# Back_Board.net
KiCad netlist of a schematic drawn in Altium Designer
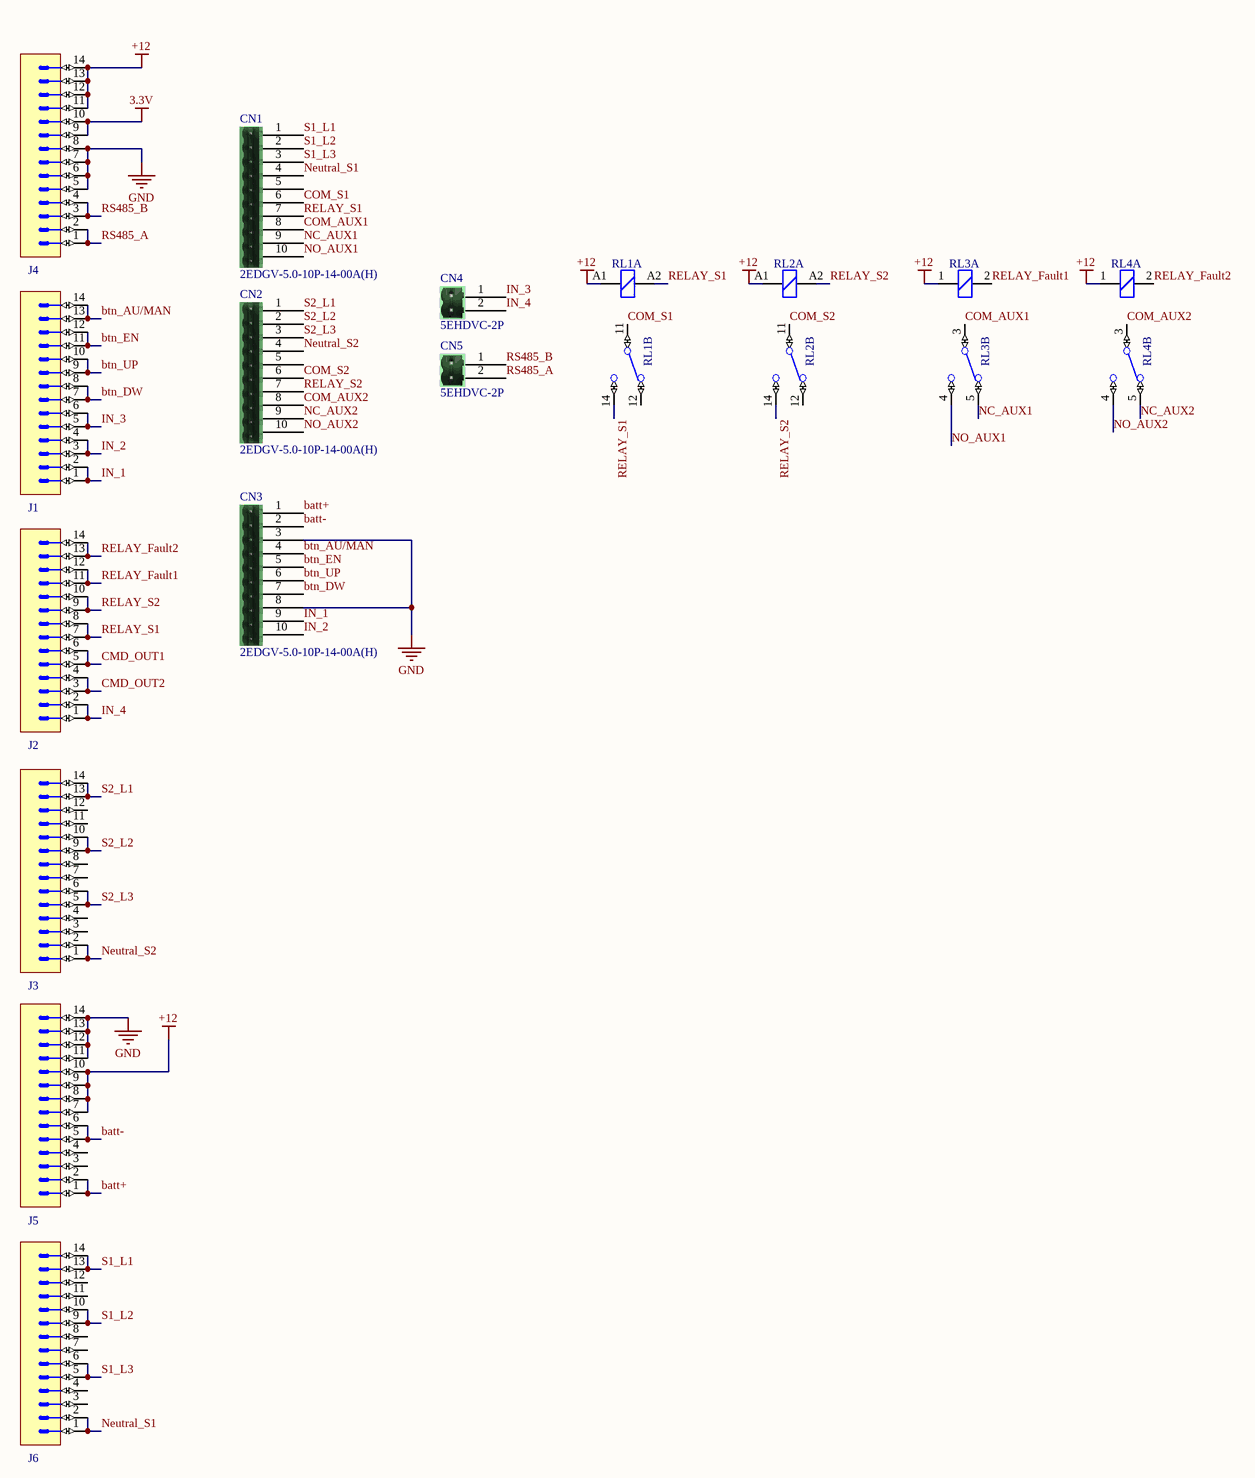
[diagram p0: Back_Board.SchDoc]

(export (version "E")
  (design (tool "Eeschema 10.0.6"))
  (components
    (comp (ref "CN1")
      (value "2EDGV-5.0-10P-14-00A(H)")
      (footprint "0330-0097-8_2EDGV-5.0-10P-14-00A(H)")
      (description "Plug-in Terminal Block 10pins,Male,300V/15A  Pitch 5.0mm")
      (fields (field (name "ES PART NUMBER") "0330-0097-8"))
      (libsource (lib "ES Terminal Blocks") (part "0330-0097-8_2EDGV-5.0-10P-14-00A(H)"))
    )
    (comp (ref "CN2")
      (value "2EDGV-5.0-10P-14-00A(H)")
      (footprint "0330-0097-8_2EDGV-5.0-10P-14-00A(H)")
      (description "Plug-in Terminal Block 10pins,Male,300V/15A  Pitch 5.0mm")
      (fields (field (name "ES PART NUMBER") "0330-0097-8"))
      (libsource (lib "ES Terminal Blocks") (part "0330-0097-8_2EDGV-5.0-10P-14-00A(H)"))
    )
    (comp (ref "CN3")
      (value "2EDGV-5.0-10P-14-00A(H)")
      (footprint "0330-0097-8_2EDGV-5.0-10P-14-00A(H)")
      (description "Plug-in Terminal Block 10pins,Male,300V/15A  Pitch 5.0mm")
      (fields (field (name "ES PART NUMBER") "0330-0097-8"))
      (libsource (lib "ES Terminal Blocks") (part "0330-0097-8_2EDGV-5.0-10P-14-00A(H)"))
    )
    (comp (ref "CN4")
      (value "5EHDVC-2P")
      (footprint "0005-0113-3_5EHDVC-2P")
      (description "Plug-in Terminal Block 2pins,Male,300V/15A  Pitch 5.00mm")
      (fields (field (name "ES PART NUMBER") "0005-0113-3"))
      (libsource (lib "ES Terminal Blocks") (part "0005-0113-3_5EHDVC-2P"))
    )
    (comp (ref "CN5")
      (value "5EHDVC-2P")
      (footprint "0005-0113-3_5EHDVC-2P")
      (description "Plug-in Terminal Block 2pins,Male,300V/15A  Pitch 5.00mm")
      (fields (field (name "ES PART NUMBER") "0005-0113-3"))
      (libsource (lib "ES Terminal Blocks") (part "0005-0113-3_5EHDVC-2P"))
    )
    (comp (ref "J1")
      (value "Header 14")
      (footprint "COMATEL_389.0358.1.14.400")
      (description "Connector 14 Male")
      (fields
        (field (name "PART NUMBER") "COMATEL_389.0358.1.14.400")
        (field (name "MANUFACTURER") "KONTEK COMATEL")
        (field (name "AUTHOR") "CERN DEM JLC")
      )
      (libsource (lib "Connectors") (part "Connector 14 Male"))
    )
    (comp (ref "J2")
      (value "Header 14")
      (footprint "COMATEL_389.0358.1.14.400")
      (description "Connector 14 Male")
      (fields
        (field (name "PART NUMBER") "COMATEL_389.0358.1.14.400")
        (field (name "MANUFACTURER") "KONTEK COMATEL")
        (field (name "AUTHOR") "CERN DEM JLC")
      )
      (libsource (lib "Connectors") (part "Connector 14 Male"))
    )
    (comp (ref "J3")
      (value "Header 14")
      (footprint "COMATEL_389.0358.1.14.400")
      (description "Connector 14 Male")
      (fields
        (field (name "PART NUMBER") "COMATEL_389.0358.1.14.400")
        (field (name "MANUFACTURER") "KONTEK COMATEL")
        (field (name "AUTHOR") "CERN DEM JLC")
      )
      (libsource (lib "Connectors") (part "Connector 14 Male"))
    )
    (comp (ref "J4")
      (value "Header 14")
      (footprint "COMATEL_389.0358.1.14.400")
      (description "Connector 14 Male")
      (fields
        (field (name "PART NUMBER") "COMATEL_389.0358.1.14.400")
        (field (name "MANUFACTURER") "KONTEK COMATEL")
        (field (name "AUTHOR") "CERN DEM JLC")
      )
      (libsource (lib "Connectors") (part "Connector 14 Male"))
    )
    (comp (ref "J5")
      (value "Header 14")
      (footprint "COMATEL_389.0358.1.14.400")
      (description "Connector 14 Male")
      (fields
        (field (name "PART NUMBER") "COMATEL_389.0358.1.14.400")
        (field (name "MANUFACTURER") "KONTEK COMATEL")
        (field (name "AUTHOR") "CERN DEM JLC")
      )
      (libsource (lib "Connectors") (part "Connector 14 Male"))
    )
    (comp (ref "J6")
      (value "Header 14")
      (footprint "COMATEL_389.0358.1.14.400")
      (description "Connector 14 Male")
      (fields
        (field (name "PART NUMBER") "COMATEL_389.0358.1.14.400")
        (field (name "MANUFACTURER") "KONTEK COMATEL")
        (field (name "AUTHOR") "CERN DEM JLC")
      )
      (libsource (lib "Connectors") (part "Connector 14 Male"))
    )
    (comp (ref "RL1")
      (value "12VDC")
      (footprint "REL_TYCO_SCHRACK_RT31XXXX")
      (description "RT PCB Relay Form C (1 CO Contact)")
      (fields
        (field (name "PART NUMBER") "REL_TYCO_SCHRACK_RT314012")
        (field (name "MANUFACTURER") "TYCO SCHRACK")
        (field (name "AUTHOR") "CERN DEM JLC")
      )
      (libsource (lib "Eletro-mechanical") (part "REL_TYCO_SCHRACK_RT31xxxx"))
    )
    (comp (ref "RL2")
      (value "12VDC")
      (footprint "REL_TYCO_SCHRACK_RT31XXXX")
      (description "RT PCB Relay Form C (1 CO Contact)")
      (fields
        (field (name "PART NUMBER") "REL_TYCO_SCHRACK_RT314012")
        (field (name "MANUFACTURER") "TYCO SCHRACK")
        (field (name "AUTHOR") "CERN DEM JLC")
      )
      (libsource (lib "Eletro-mechanical") (part "REL_TYCO_SCHRACK_RT31xxxx"))
    )
    (comp (ref "RL3")
      (value "5VDC")
      (footprint "REL_FINDER_36.11")
      (description "10A SPDT PCB Relay, 36 Serie")
      (fields
        (field (name "PART NUMBER") "REL_FINDER_36.11.9.005.4001")
        (field (name "MANUFACTURER") "FINDER")
        (field (name "AUTHOR") "CERN DEM JLC")
      )
      (libsource (lib "Eletro-mechanical") (part "REL_FINDER_36.11-4001"))
    )
    (comp (ref "RL4")
      (value "5VDC")
      (footprint "REL_FINDER_36.11")
      (description "10A SPDT PCB Relay, 36 Serie")
      (fields
        (field (name "PART NUMBER") "REL_FINDER_36.11.9.005.4001")
        (field (name "MANUFACTURER") "FINDER")
        (field (name "AUTHOR") "CERN DEM JLC")
      )
      (libsource (lib "Eletro-mechanical") (part "REL_FINDER_36.11-4001"))
    )
  )
  (nets
    (net (code "1") (name "+12") (class "Default")
      (node (ref "J4") (pin "11") (pinfunction "11_11") (pintype "bidirectional"))
      (node (ref "J4") (pin "12") (pinfunction "12_12") (pintype "bidirectional"))
      (node (ref "J4") (pin "13") (pinfunction "13_13") (pintype "bidirectional"))
      (node (ref "J4") (pin "14") (pinfunction "14_14") (pintype "bidirectional"))
      (node (ref "J5") (pin "10") (pinfunction "10_10") (pintype "bidirectional"))
      (node (ref "J5") (pin "7") (pinfunction "7_7") (pintype "bidirectional"))
      (node (ref "J5") (pin "8") (pinfunction "8_8") (pintype "bidirectional"))
      (node (ref "J5") (pin "9") (pinfunction "9_9") (pintype "bidirectional"))
      (node (ref "RL1") (pin "A1") (pinfunction "A1_A1") (pintype "passive"))
      (node (ref "RL2") (pin "A1") (pinfunction "A1_A1") (pintype "passive"))
      (node (ref "RL3") (pin "1") (pinfunction "COIL_1") (pintype "passive"))
      (node (ref "RL4") (pin "1") (pinfunction "COIL_1") (pintype "passive"))
    )
    (net (code "2") (name "/CMD_OUT1") (class "Default")
      (node (ref "J2") (pin "5") (pinfunction "5_5") (pintype "bidirectional"))
      (node (ref "J2") (pin "6") (pinfunction "6_6") (pintype "bidirectional"))
    )
    (net (code "3") (name "/CMD_OUT2") (class "Default")
      (node (ref "J2") (pin "3") (pinfunction "3_3") (pintype "bidirectional"))
      (node (ref "J2") (pin "4") (pinfunction "4_4") (pintype "bidirectional"))
    )
    (net (code "4") (name "/COM_AUX1") (class "Default")
      (node (ref "CN1") (pin "8") (pinfunction "8_8") (pintype "passive"))
      (node (ref "RL3") (pin "3") (pinfunction "C_3") (pintype "bidirectional"))
    )
    (net (code "5") (name "/COM_AUX2") (class "Default")
      (node (ref "CN2") (pin "8") (pinfunction "8_8") (pintype "passive"))
      (node (ref "RL4") (pin "3") (pinfunction "C_3") (pintype "bidirectional"))
    )
    (net (code "6") (name "/COM_S1") (class "Default")
      (node (ref "CN1") (pin "6") (pinfunction "6_6") (pintype "passive"))
      (node (ref "RL1") (pin "11") (pinfunction "C_11") (pintype "bidirectional"))
    )
    (net (code "7") (name "/COM_S2") (class "Default")
      (node (ref "CN2") (pin "6") (pinfunction "6_6") (pintype "passive"))
      (node (ref "RL2") (pin "11") (pinfunction "C_11") (pintype "bidirectional"))
    )
    (net (code "8") (name "/IN_1") (class "Default")
      (node (ref "CN3") (pin "9") (pinfunction "9_9") (pintype "passive"))
      (node (ref "J1") (pin "1") (pinfunction "1_1") (pintype "bidirectional"))
      (node (ref "J1") (pin "2") (pinfunction "2_2") (pintype "bidirectional"))
    )
    (net (code "9") (name "/IN_2") (class "Default")
      (node (ref "CN3") (pin "10") (pinfunction "10_10") (pintype "passive"))
      (node (ref "J1") (pin "3") (pinfunction "3_3") (pintype "bidirectional"))
      (node (ref "J1") (pin "4") (pinfunction "4_4") (pintype "bidirectional"))
    )
    (net (code "10") (name "/IN_3") (class "Default")
      (node (ref "CN4") (pin "1") (pinfunction "1_1") (pintype "passive"))
      (node (ref "J1") (pin "5") (pinfunction "5_5") (pintype "bidirectional"))
      (node (ref "J1") (pin "6") (pinfunction "6_6") (pintype "bidirectional"))
    )
    (net (code "11") (name "/IN_4") (class "Default")
      (node (ref "CN4") (pin "2") (pinfunction "2_2") (pintype "passive"))
      (node (ref "J2") (pin "1") (pinfunction "1_1") (pintype "bidirectional"))
      (node (ref "J2") (pin "2") (pinfunction "2_2") (pintype "bidirectional"))
    )
    (net (code "12") (name "/NC_AUX1") (class "Default")
      (node (ref "CN1") (pin "9") (pinfunction "9_9") (pintype "passive"))
      (node (ref "RL3") (pin "5") (pinfunction "NC_5") (pintype "bidirectional"))
    )
    (net (code "13") (name "/NC_AUX2") (class "Default")
      (node (ref "CN2") (pin "9") (pinfunction "9_9") (pintype "passive"))
      (node (ref "RL4") (pin "5") (pinfunction "NC_5") (pintype "bidirectional"))
    )
    (net (code "14") (name "/NO_AUX1") (class "Default")
      (node (ref "CN1") (pin "10") (pinfunction "10_10") (pintype "passive"))
      (node (ref "RL3") (pin "4") (pinfunction "NO_4") (pintype "bidirectional"))
    )
    (net (code "15") (name "/NO_AUX2") (class "Default")
      (node (ref "CN2") (pin "10") (pinfunction "10_10") (pintype "passive"))
      (node (ref "RL4") (pin "4") (pinfunction "NO_4") (pintype "bidirectional"))
    )
    (net (code "16") (name "/Neutral_S1") (class "Default")
      (node (ref "CN1") (pin "4") (pinfunction "4_4") (pintype "passive"))
      (node (ref "J6") (pin "1") (pinfunction "1_1") (pintype "bidirectional"))
      (node (ref "J6") (pin "2") (pinfunction "2_2") (pintype "bidirectional"))
    )
    (net (code "17") (name "/Neutral_S2") (class "Default")
      (node (ref "CN2") (pin "4") (pinfunction "4_4") (pintype "passive"))
      (node (ref "J3") (pin "1") (pinfunction "1_1") (pintype "bidirectional"))
      (node (ref "J3") (pin "2") (pinfunction "2_2") (pintype "bidirectional"))
    )
    (net (code "18") (name "/RELAY_Fault1") (class "Default")
      (node (ref "J2") (pin "11") (pinfunction "11_11") (pintype "bidirectional"))
      (node (ref "J2") (pin "12") (pinfunction "12_12") (pintype "bidirectional"))
      (node (ref "RL3") (pin "2") (pinfunction "COIL_2") (pintype "passive"))
    )
    (net (code "19") (name "/RELAY_Fault2") (class "Default")
      (node (ref "J2") (pin "13") (pinfunction "13_13") (pintype "bidirectional"))
      (node (ref "J2") (pin "14") (pinfunction "14_14") (pintype "bidirectional"))
      (node (ref "RL4") (pin "2") (pinfunction "COIL_2") (pintype "passive"))
    )
    (net (code "20") (name "/RELAY_S1") (class "Default")
      (node (ref "CN1") (pin "7") (pinfunction "7_7") (pintype "passive"))
      (node (ref "J2") (pin "7") (pinfunction "7_7") (pintype "bidirectional"))
      (node (ref "J2") (pin "8") (pinfunction "8_8") (pintype "bidirectional"))
      (node (ref "RL1") (pin "14") (pinfunction "NO_14") (pintype "bidirectional"))
      (node (ref "RL1") (pin "A2") (pinfunction "A2_A2") (pintype "passive"))
    )
    (net (code "21") (name "/RELAY_S2") (class "Default")
      (node (ref "CN2") (pin "7") (pinfunction "7_7") (pintype "passive"))
      (node (ref "J2") (pin "10") (pinfunction "10_10") (pintype "bidirectional"))
      (node (ref "J2") (pin "9") (pinfunction "9_9") (pintype "bidirectional"))
      (node (ref "RL2") (pin "14") (pinfunction "NO_14") (pintype "bidirectional"))
      (node (ref "RL2") (pin "A2") (pinfunction "A2_A2") (pintype "passive"))
    )
    (net (code "22") (name "/RS485_A") (class "Default")
      (node (ref "CN5") (pin "2") (pinfunction "2_2") (pintype "passive"))
      (node (ref "J4") (pin "1") (pinfunction "1_1") (pintype "bidirectional"))
      (node (ref "J4") (pin "2") (pinfunction "2_2") (pintype "bidirectional"))
    )
    (net (code "23") (name "/RS485_B") (class "Default")
      (node (ref "CN5") (pin "1") (pinfunction "1_1") (pintype "passive"))
      (node (ref "J4") (pin "3") (pinfunction "3_3") (pintype "bidirectional"))
      (node (ref "J4") (pin "4") (pinfunction "4_4") (pintype "bidirectional"))
    )
    (net (code "24") (name "/S1_L1") (class "Default")
      (node (ref "CN1") (pin "1") (pinfunction "1_1") (pintype "passive"))
      (node (ref "J6") (pin "13") (pinfunction "13_13") (pintype "bidirectional"))
      (node (ref "J6") (pin "14") (pinfunction "14_14") (pintype "bidirectional"))
    )
    (net (code "25") (name "/S1_L2") (class "Default")
      (node (ref "CN1") (pin "2") (pinfunction "2_2") (pintype "passive"))
      (node (ref "J6") (pin "10") (pinfunction "10_10") (pintype "bidirectional"))
      (node (ref "J6") (pin "9") (pinfunction "9_9") (pintype "bidirectional"))
    )
    (net (code "26") (name "/S1_L3") (class "Default")
      (node (ref "CN1") (pin "3") (pinfunction "3_3") (pintype "passive"))
      (node (ref "J6") (pin "5") (pinfunction "5_5") (pintype "bidirectional"))
      (node (ref "J6") (pin "6") (pinfunction "6_6") (pintype "bidirectional"))
    )
    (net (code "27") (name "/S2_L1") (class "Default")
      (node (ref "CN2") (pin "1") (pinfunction "1_1") (pintype "passive"))
      (node (ref "J3") (pin "13") (pinfunction "13_13") (pintype "bidirectional"))
      (node (ref "J3") (pin "14") (pinfunction "14_14") (pintype "bidirectional"))
    )
    (net (code "28") (name "/S2_L2") (class "Default")
      (node (ref "CN2") (pin "2") (pinfunction "2_2") (pintype "passive"))
      (node (ref "J3") (pin "10") (pinfunction "10_10") (pintype "bidirectional"))
      (node (ref "J3") (pin "9") (pinfunction "9_9") (pintype "bidirectional"))
    )
    (net (code "29") (name "/S2_L3") (class "Default")
      (node (ref "CN2") (pin "3") (pinfunction "3_3") (pintype "passive"))
      (node (ref "J3") (pin "5") (pinfunction "5_5") (pintype "bidirectional"))
      (node (ref "J3") (pin "6") (pinfunction "6_6") (pintype "bidirectional"))
    )
    (net (code "30") (name "/batt+") (class "Default")
      (node (ref "CN3") (pin "1") (pinfunction "1_1") (pintype "passive"))
      (node (ref "J5") (pin "1") (pinfunction "1_1") (pintype "bidirectional"))
      (node (ref "J5") (pin "2") (pinfunction "2_2") (pintype "bidirectional"))
    )
    (net (code "31") (name "/batt-") (class "Default")
      (node (ref "CN3") (pin "2") (pinfunction "2_2") (pintype "passive"))
      (node (ref "J5") (pin "5") (pinfunction "5_5") (pintype "bidirectional"))
      (node (ref "J5") (pin "6") (pinfunction "6_6") (pintype "bidirectional"))
    )
    (net (code "32") (name "/btn_AU{slash}MAN") (class "Default")
      (node (ref "CN3") (pin "4") (pinfunction "4_4") (pintype "passive"))
      (node (ref "J1") (pin "13") (pinfunction "13_13") (pintype "bidirectional"))
      (node (ref "J1") (pin "14") (pinfunction "14_14") (pintype "bidirectional"))
    )
    (net (code "33") (name "/btn_DW") (class "Default")
      (node (ref "CN3") (pin "7") (pinfunction "7_7") (pintype "passive"))
      (node (ref "J1") (pin "7") (pinfunction "7_7") (pintype "bidirectional"))
      (node (ref "J1") (pin "8") (pinfunction "8_8") (pintype "bidirectional"))
    )
    (net (code "34") (name "/btn_EN") (class "Default")
      (node (ref "CN3") (pin "5") (pinfunction "5_5") (pintype "passive"))
      (node (ref "J1") (pin "11") (pinfunction "11_11") (pintype "bidirectional"))
      (node (ref "J1") (pin "12") (pinfunction "12_12") (pintype "bidirectional"))
    )
    (net (code "35") (name "/btn_UP") (class "Default")
      (node (ref "CN3") (pin "6") (pinfunction "6_6") (pintype "passive"))
      (node (ref "J1") (pin "10") (pinfunction "10_10") (pintype "bidirectional"))
      (node (ref "J1") (pin "9") (pinfunction "9_9") (pintype "bidirectional"))
    )
    (net (code "36") (name "3.3V") (class "Default")
      (node (ref "J4") (pin "10") (pinfunction "10_10") (pintype "bidirectional"))
      (node (ref "J4") (pin "9") (pinfunction "9_9") (pintype "bidirectional"))
    )
    (net (code "37") (name "GND") (class "Default")
      (node (ref "CN3") (pin "3") (pinfunction "3_3") (pintype "passive"))
      (node (ref "CN3") (pin "8") (pinfunction "8_8") (pintype "passive"))
      (node (ref "J4") (pin "5") (pinfunction "5_5") (pintype "bidirectional"))
      (node (ref "J4") (pin "6") (pinfunction "6_6") (pintype "bidirectional"))
      (node (ref "J4") (pin "7") (pinfunction "7_7") (pintype "bidirectional"))
      (node (ref "J4") (pin "8") (pinfunction "8_8") (pintype "bidirectional"))
      (node (ref "J5") (pin "11") (pinfunction "11_11") (pintype "bidirectional"))
      (node (ref "J5") (pin "12") (pinfunction "12_12") (pintype "bidirectional"))
      (node (ref "J5") (pin "13") (pinfunction "13_13") (pintype "bidirectional"))
      (node (ref "J5") (pin "14") (pinfunction "14_14") (pintype "bidirectional"))
    )
    (net (code "38") (name "unconnected-(CN1-Pad5)") (class "Default")
      (node (ref "CN1") (pin "5") (pinfunction "5_5") (pintype "passive"))
    )
    (net (code "39") (name "unconnected-(CN2-Pad5)") (class "Default")
      (node (ref "CN2") (pin "5") (pinfunction "5_5") (pintype "passive"))
    )
    (net (code "40") (name "unconnected-(J3-Pad3)") (class "Default")
      (node (ref "J3") (pin "3") (pinfunction "3_3") (pintype "bidirectional"))
    )
    (net (code "41") (name "unconnected-(J3-Pad4)") (class "Default")
      (node (ref "J3") (pin "4") (pinfunction "4_4") (pintype "bidirectional"))
    )
    (net (code "42") (name "unconnected-(J3-Pad7)") (class "Default")
      (node (ref "J3") (pin "7") (pinfunction "7_7") (pintype "bidirectional"))
    )
    (net (code "43") (name "unconnected-(J3-Pad8)") (class "Default")
      (node (ref "J3") (pin "8") (pinfunction "8_8") (pintype "bidirectional"))
    )
    (net (code "44") (name "unconnected-(J3-Pad11)") (class "Default")
      (node (ref "J3") (pin "11") (pinfunction "11_11") (pintype "bidirectional"))
    )
    (net (code "45") (name "unconnected-(J3-Pad12)") (class "Default")
      (node (ref "J3") (pin "12") (pinfunction "12_12") (pintype "bidirectional"))
    )
    (net (code "46") (name "unconnected-(J5-Pad3)") (class "Default")
      (node (ref "J5") (pin "3") (pinfunction "3_3") (pintype "bidirectional"))
    )
    (net (code "47") (name "unconnected-(J5-Pad4)") (class "Default")
      (node (ref "J5") (pin "4") (pinfunction "4_4") (pintype "bidirectional"))
    )
    (net (code "48") (name "unconnected-(J6-Pad3)") (class "Default")
      (node (ref "J6") (pin "3") (pinfunction "3_3") (pintype "bidirectional"))
    )
    (net (code "49") (name "unconnected-(J6-Pad4)") (class "Default")
      (node (ref "J6") (pin "4") (pinfunction "4_4") (pintype "bidirectional"))
    )
    (net (code "50") (name "unconnected-(J6-Pad7)") (class "Default")
      (node (ref "J6") (pin "7") (pinfunction "7_7") (pintype "bidirectional"))
    )
    (net (code "51") (name "unconnected-(J6-Pad8)") (class "Default")
      (node (ref "J6") (pin "8") (pinfunction "8_8") (pintype "bidirectional"))
    )
    (net (code "52") (name "unconnected-(J6-Pad11)") (class "Default")
      (node (ref "J6") (pin "11") (pinfunction "11_11") (pintype "bidirectional"))
    )
    (net (code "53") (name "unconnected-(J6-Pad12)") (class "Default")
      (node (ref "J6") (pin "12") (pinfunction "12_12") (pintype "bidirectional"))
    )
    (net (code "54") (name "unconnected-(RL1B-NC-Pad12)") (class "Default")
      (node (ref "RL1") (pin "12") (pinfunction "NC_12") (pintype "bidirectional"))
    )
    (net (code "55") (name "unconnected-(RL2B-NC-Pad12)") (class "Default")
      (node (ref "RL2") (pin "12") (pinfunction "NC_12") (pintype "bidirectional"))
    )
  )
)
